# ife18_TS_AIL_Buck.net
KiCad netlist of a schematic drawn in Altium Designer
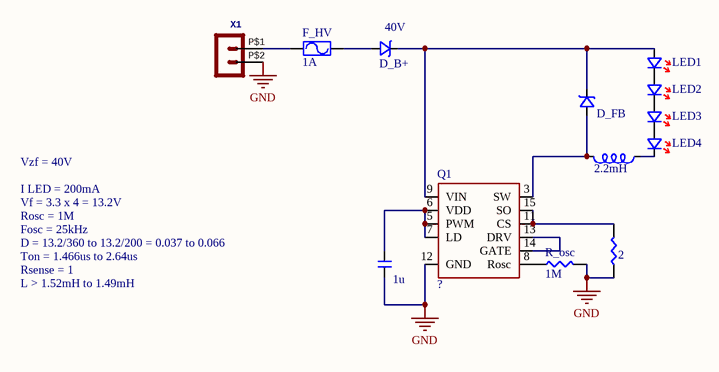
[diagram p0: ife18_TS_AIL_Buck.SchDoc]

(export (version "E")
  (design (tool "Eeschema 10.0.6"))
  (components
    (comp (ref "C_VDD")
      (value "1u")
      (footprint "CAP-0603")
      (libsource (lib "ife19_Elec_Library") (part "CAP-0603"))
    )
    (comp (ref "D_B+")
      (value "40V")
      (footprint "SMB")
      (libsource (lib "ife19_Elec_Library") (part "DIODE-SMB"))
    )
    (comp (ref "D_FB")
      (value "?")
      (footprint "SMB")
      (libsource (lib "ife19_Elec_Library") (part "DIODE-SMB"))
    )
    (comp (ref "F_HV")
      (value "1A")
      (footprint "FUSE_885")
      (libsource (lib "ife19_Elec_Library") (part "FUSE_885"))
    )
    (comp (ref "IND")
      (value "2.2mH")
      (footprint "IND-8080")
      (libsource (lib "ife19_Elec_Library") (part "IND-8080"))
    )
    (comp (ref "LED1")
      (value "LED XQA Red")
      (footprint "LED_XQARED")
      (libsource (lib "ife19_Elec_Library") (part "LED_XQARED"))
    )
    (comp (ref "LED2")
      (value "LED XQA Red")
      (footprint "LED_XQARED")
      (libsource (lib "ife19_Elec_Library") (part "LED_XQARED"))
    )
    (comp (ref "LED3")
      (value "LED XQA Red")
      (footprint "LED_XQARED")
      (libsource (lib "ife19_Elec_Library") (part "LED_XQARED"))
    )
    (comp (ref "LED4")
      (value "LED XQA Red")
      (footprint "LED_XQARED")
      (libsource (lib "ife19_Elec_Library") (part "LED_XQARED"))
    )
    (comp (ref "Q1")
      (value "?")
      (footprint "SO-16")
      (libsource (lib "ife19_Elec_Library") (part "IC-SO16_AL9901_1"))
    )
    (comp (ref "R_osc")
      (value "1M")
      (footprint "RES-0603")
      (libsource (lib "ife19_Elec_Library") (part "RES-0603"))
    )
    (comp (ref "R_sense")
      (value "2")
      (footprint "RES-0603")
      (libsource (lib "ife19_Elec_Library") (part "RES-0603"))
    )
    (comp (ref "X1")
      (value "Molex - Micro-Fit 3.0 Series connector,  3.00mm (0.118\") pitch header, 2 positions.")
      (footprint "43650-0224")
      (libsource (lib "ife19_Elec_Conn_Library") (part "POS2_MF43650-0224"))
    )
  )
  (nets
    (net (code "1") (name "GND") (class "Default")
      (node (ref "C_VDD") (pin "1") (pinfunction "1_1") (pintype "passive"))
      (node (ref "Q1") (pin "12") (pinfunction "GND_12") (pintype "passive"))
      (node (ref "R_osc") (pin "2") (pinfunction "2_2") (pintype "passive"))
      (node (ref "R_sense") (pin "1") (pinfunction "1_1") (pintype "passive"))
      (node (ref "X1") (pin "P$2") (pinfunction "2_P$2") (pintype "passive"))
    )
    (net (code "2") (name "Net-(D_B+-PadA)") (class "Default")
      (node (ref "D_B+") (pin "A") (pinfunction "A_A") (pintype "passive"))
      (node (ref "F_HV") (pin "1") (pinfunction "1_1") (pintype "passive"))
    )
    (net (code "3") (name "Net-(IND-Pad1)") (class "Default")
      (node (ref "IND") (pin "1") (pinfunction "1_1") (pintype "passive"))
      (node (ref "LED4") (pin "K") (pinfunction "K_K") (pintype "passive"))
    )
    (net (code "4") (name "Net-(LED1-PadK)") (class "Default")
      (node (ref "LED1") (pin "K") (pinfunction "K_K") (pintype "passive"))
      (node (ref "LED2") (pin "A") (pinfunction "A_A") (pintype "passive"))
    )
    (net (code "5") (name "Net-(LED2-PadK)") (class "Default")
      (node (ref "LED2") (pin "K") (pinfunction "K_K") (pintype "passive"))
      (node (ref "LED3") (pin "A") (pinfunction "A_A") (pintype "passive"))
    )
    (net (code "6") (name "Net-(LED3-PadK)") (class "Default")
      (node (ref "LED3") (pin "K") (pinfunction "K_K") (pintype "passive"))
      (node (ref "LED4") (pin "A") (pinfunction "A_A") (pintype "passive"))
    )
    (net (code "7") (name "Net-(Q1-CS)") (class "Default")
      (node (ref "Q1") (pin "11") (pinfunction "CS_11") (pintype "passive"))
      (node (ref "Q1") (pin "15") (pinfunction "SO_15") (pintype "passive"))
      (node (ref "R_sense") (pin "2") (pinfunction "2_2") (pintype "passive"))
    )
    (net (code "8") (name "Net-(Q1-DRV)") (class "Default")
      (node (ref "Q1") (pin "13") (pinfunction "DRV_13") (pintype "passive"))
      (node (ref "Q1") (pin "14") (pinfunction "GATE_14") (pintype "passive"))
    )
    (net (code "9") (name "Net-(Q1-LD)") (class "Default")
      (node (ref "C_VDD") (pin "2") (pinfunction "2_2") (pintype "passive"))
      (node (ref "Q1") (pin "5") (pinfunction "PWM_5") (pintype "passive"))
      (node (ref "Q1") (pin "6") (pinfunction "VDD_6") (pintype "passive"))
      (node (ref "Q1") (pin "7") (pinfunction "LD_7") (pintype "passive"))
    )
    (net (code "10") (name "Net-(Q1-Rosc)") (class "Default")
      (node (ref "Q1") (pin "8") (pinfunction "Rosc_8") (pintype "passive"))
      (node (ref "R_osc") (pin "1") (pinfunction "1_1") (pintype "passive"))
    )
    (net (code "11") (name "Net-(Q1-SW)") (class "Default")
      (node (ref "D_FB") (pin "A") (pinfunction "A_A") (pintype "passive"))
      (node (ref "IND") (pin "2") (pinfunction "2_2") (pintype "passive"))
      (node (ref "Q1") (pin "3") (pinfunction "SW_3") (pintype "passive"))
    )
    (net (code "12") (name "Net-(Q1-VIN)") (class "Default")
      (node (ref "D_B+") (pin "K") (pinfunction "K_K") (pintype "passive"))
      (node (ref "D_FB") (pin "K") (pinfunction "K_K") (pintype "passive"))
      (node (ref "LED1") (pin "A") (pinfunction "A_A") (pintype "passive"))
      (node (ref "Q1") (pin "9") (pinfunction "VIN_9") (pintype "passive"))
    )
    (net (code "13") (name "Net-(X1-1)") (class "Default")
      (node (ref "F_HV") (pin "2") (pinfunction "2_2") (pintype "passive"))
      (node (ref "X1") (pin "P$1") (pinfunction "1_P$1") (pintype "passive"))
    )
  )
)
